# TCRME_lab3.net
KiCad netlist of a schematic drawn in Altium Designer
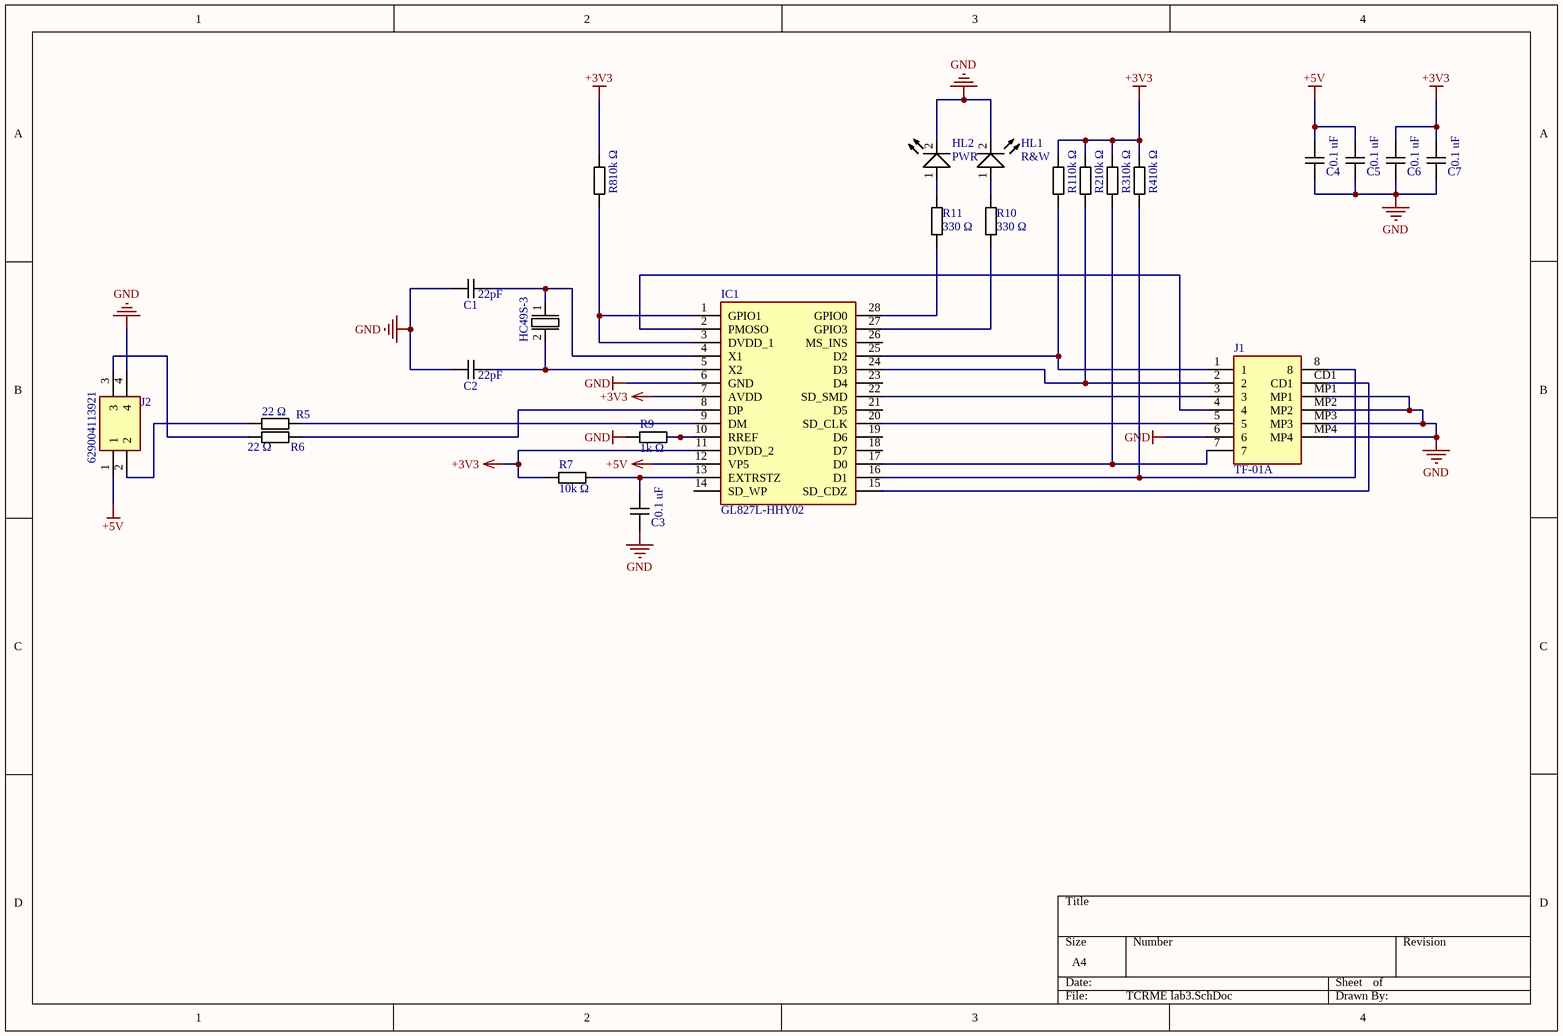
[diagram p0: TCRME lab3.SchDoc]

(export (version "E")
  (design (tool "Eeschema 10.0.6"))
  (components
    (comp (ref "C1")
      (value "22pF")
      (footprint "1206")
      (description "Cap Cer MLCC SMD 220pF 250V X7R 20% 1206")
      (fields
        (field (name "PART NUMBER") "1206B221M251CT")
        (field (name "MOUSER PART NUMBER") "791-1206B221M251CT")
      )
      (libsource (lib "SssAccesDatbase") (part "Cap"))
    )
    (comp (ref "C2")
      (value "22pF")
      (footprint "1206")
      (description "Cap Cer MLCC SMD 220pF 250V X7R 20% 1206")
      (fields
        (field (name "PART NUMBER") "1206B221M251CT")
        (field (name "MOUSER PART NUMBER") "791-1206B221M251CT")
      )
      (libsource (lib "SssAccesDatbase") (part "Cap"))
    )
    (comp (ref "C3")
      (value "0.1 uF")
      (footprint "1206")
      (description "Cap Cer MLCC SMD 220pF 250V X7R 20% 1206")
      (fields
        (field (name "PART NUMBER") "1206B221M251CT")
        (field (name "MOUSER PART NUMBER") "791-1206B221M251CT")
      )
      (libsource (lib "SssAccesDatbase") (part "Cap"))
    )
    (comp (ref "C4")
      (value "0.1 uF")
      (footprint "1206")
      (description "Cap Cer MLCC SMD 220pF 250V X7R 20% 1206")
      (fields
        (field (name "PART NUMBER") "1206B221M251CT")
        (field (name "MOUSER PART NUMBER") "791-1206B221M251CT")
      )
      (libsource (lib "SssAccesDatbase") (part "Cap"))
    )
    (comp (ref "C5")
      (value "0.1 uF")
      (footprint "1206")
      (description "Cap Cer MLCC SMD 220pF 250V X7R 20% 1206")
      (fields
        (field (name "PART NUMBER") "1206B221M251CT")
        (field (name "MOUSER PART NUMBER") "791-1206B221M251CT")
      )
      (libsource (lib "SssAccesDatbase") (part "Cap"))
    )
    (comp (ref "C6")
      (value "0.1 uF")
      (footprint "1206")
      (description "Cap Cer MLCC SMD 220pF 250V X7R 20% 1206")
      (fields
        (field (name "PART NUMBER") "1206B221M251CT")
        (field (name "MOUSER PART NUMBER") "791-1206B221M251CT")
      )
      (libsource (lib "SssAccesDatbase") (part "Cap"))
    )
    (comp (ref "C7")
      (value "0.1 uF")
      (footprint "1206")
      (description "Cap Cer MLCC SMD 220pF 250V X7R 20% 1206")
      (fields
        (field (name "PART NUMBER") "1206B221M251CT")
        (field (name "MOUSER PART NUMBER") "791-1206B221M251CT")
      )
      (libsource (lib "SssAccesDatbase") (part "Cap"))
    )
    (comp (ref "HL1")
      (value "R&W")
      (footprint "LED_3MM_GREEN")
      (fields (field (name "PART NUMBER") "FYL-5013 GD"))
      (libsource (lib "SssAccesDatbase") (part "LED_12"))
    )
    (comp (ref "HL2")
      (value "PWR")
      (footprint "LED_3MM_GREEN")
      (fields (field (name "PART NUMBER") "FYL-5013 GD"))
      (libsource (lib "SssAccesDatbase") (part "LED_12"))
    )
    (comp (ref "IC1")
      (value "GL827L-HHY02")
      (footprint "SamacSys:SOP64P600X175-28N")
      (description "Integrated Circuit")
      (libsource (lib "SamacSys") (part "GL827L-HHY02"))
    )
    (comp (ref "J1")
      (value "TF-01A")
      (footprint "SamacSys:TF01A")
      (description "Connector - Card Sockets 8 1.1mm SMD RoHS")
      (libsource (lib "SamacSys") (part "TF-01A"))
    )
    (comp (ref "J2")
      (value "629004113921")
      (footprint "SamacSys:629004113921")
      (description "Connector")
      (fields (field (name "MOUSER PART NUMBER") "710-629004113921"))
      (libsource (lib "*") (part "629004113921"))
    )
    (comp (ref "R1")
      (value "10k Ω")
      (footprint "RESC1608(0603)N")
      (description "RES SMD 0603 137k 1% 50ppm")
      (fields
        (field (name "PART NUMBER") "CPF0603F137KC1")
        (field (name "MOUSER PART NUMBER") "279-CPF0603F137KC1")
      )
      (libsource (lib "") (part "Resistor general_1"))
    )
    (comp (ref "R2")
      (value "10k Ω")
      (footprint "RESC1608(0603)N")
      (description "RES SMD 0603 137k 1% 50ppm")
      (fields
        (field (name "PART NUMBER") "CPF0603F137KC1")
        (field (name "MOUSER PART NUMBER") "279-CPF0603F137KC1")
      )
      (libsource (lib "") (part "Resistor general_1"))
    )
    (comp (ref "R3")
      (value "10k Ω")
      (footprint "RESC1608(0603)N")
      (description "RES SMD 0603 137k 1% 50ppm")
      (fields
        (field (name "PART NUMBER") "CPF0603F137KC1")
        (field (name "MOUSER PART NUMBER") "279-CPF0603F137KC1")
      )
      (libsource (lib "") (part "Resistor general_1"))
    )
    (comp (ref "R4")
      (value "10k Ω")
      (footprint "RESC1608(0603)N")
      (description "RES SMD 0603 137k 1% 50ppm")
      (fields
        (field (name "PART NUMBER") "CPF0603F137KC1")
        (field (name "MOUSER PART NUMBER") "279-CPF0603F137KC1")
      )
      (libsource (lib "") (part "Resistor general_1"))
    )
    (comp (ref "R5")
      (value "22 Ω")
      (footprint "RESC1608(0603)N")
      (description "RES SMD 0603 137k 1% 50ppm")
      (fields
        (field (name "PART NUMBER") "CPF0603F137KC1")
        (field (name "MOUSER PART NUMBER") "279-CPF0603F137KC1")
      )
      (libsource (lib "") (part "Resistor general_3"))
    )
    (comp (ref "R6")
      (value "22 Ω")
      (footprint "RESC1608(0603)N")
      (description "RES SMD 0603 137k 1% 50ppm")
      (fields
        (field (name "PART NUMBER") "CPF0603F137KC1")
        (field (name "MOUSER PART NUMBER") "279-CPF0603F137KC1")
      )
      (libsource (lib "") (part "Resistor general_2"))
    )
    (comp (ref "R7")
      (value "10k Ω")
      (footprint "RESC1608(0603)N")
      (description "RES SMD 0603 137k 1% 50ppm")
      (fields
        (field (name "PART NUMBER") "CPF0603F137KC1")
        (field (name "MOUSER PART NUMBER") "279-CPF0603F137KC1")
      )
      (libsource (lib "") (part "Resistor general_2"))
    )
    (comp (ref "R8")
      (value "10k Ω")
      (footprint "RESC1608(0603)N")
      (description "RES SMD 0603 137k 1% 50ppm")
      (fields
        (field (name "PART NUMBER") "CPF0603F137KC1")
        (field (name "MOUSER PART NUMBER") "279-CPF0603F137KC1")
      )
      (libsource (lib "") (part "Resistor general_1"))
    )
    (comp (ref "R9")
      (value "1k Ω")
      (footprint "RESC1608(0603)N")
      (description "RES SMD 0603 137k 1% 50ppm")
      (fields
        (field (name "PART NUMBER") "CPF0603F137KC1")
        (field (name "MOUSER PART NUMBER") "279-CPF0603F137KC1")
      )
      (libsource (lib "") (part "Resistor general_2"))
    )
    (comp (ref "R10")
      (value "330 Ω")
      (footprint "RESC1608(0603)N")
      (description "RES SMD 0603 137k 1% 50ppm")
      (fields
        (field (name "PART NUMBER") "CPF0603F137KC1")
        (field (name "MOUSER PART NUMBER") "279-CPF0603F137KC1")
      )
      (libsource (lib "SssAccesDatbase") (part "Resistor general"))
    )
    (comp (ref "R11")
      (value "330 Ω")
      (footprint "RESC1608(0603)N")
      (description "RES SMD 0603 137k 1% 50ppm")
      (fields
        (field (name "PART NUMBER") "CPF0603F137KC1")
        (field (name "MOUSER PART NUMBER") "279-CPF0603F137KC1")
      )
      (libsource (lib "SssAccesDatbase") (part "Resistor general"))
    )
    (comp (ref "Y1")
      (value "HC49S-3")
      (footprint "HC49S-3")
      (libsource (lib "Database_Libs2") (part "HC49S-3"))
    )
  )
  (nets
    (net (code "1") (name "+3V3") (class "Default")
      (node (ref "C6") (pin "2") (pinfunction "2_2") (pintype "passive"))
      (node (ref "C7") (pin "2") (pinfunction "2_2") (pintype "passive"))
      (node (ref "IC1") (pin "11") (pinfunction "DVDD_2_11") (pintype "passive"))
      (node (ref "IC1") (pin "7") (pinfunction "AVDD_7") (pintype "passive"))
      (node (ref "R1") (pin "2") (pinfunction "2_2") (pintype "passive"))
      (node (ref "R2") (pin "2") (pinfunction "2_2") (pintype "passive"))
      (node (ref "R3") (pin "2") (pinfunction "2_2") (pintype "passive"))
      (node (ref "R4") (pin "2") (pinfunction "2_2") (pintype "passive"))
      (node (ref "R7") (pin "2") (pinfunction "2_2") (pintype "passive"))
      (node (ref "R8") (pin "2") (pinfunction "2_2") (pintype "passive"))
    )
    (net (code "2") (name "+5V") (class "Default")
      (node (ref "C4") (pin "2") (pinfunction "2_2") (pintype "passive"))
      (node (ref "C5") (pin "2") (pinfunction "2_2") (pintype "passive"))
      (node (ref "IC1") (pin "12") (pinfunction "VP5_12") (pintype "passive"))
      (node (ref "J2") (pin "1") (pinfunction "1_1") (pintype "passive"))
    )
    (net (code "3") (name "GND") (class "Default")
      (node (ref "C1") (pin "1") (pinfunction "1_1") (pintype "passive"))
      (node (ref "C2") (pin "1") (pinfunction "1_1") (pintype "passive"))
      (node (ref "C3") (pin "1") (pinfunction "1_1") (pintype "passive"))
      (node (ref "C4") (pin "1") (pinfunction "1_1") (pintype "passive"))
      (node (ref "C5") (pin "1") (pinfunction "1_1") (pintype "passive"))
      (node (ref "C6") (pin "1") (pinfunction "1_1") (pintype "passive"))
      (node (ref "C7") (pin "1") (pinfunction "1_1") (pintype "passive"))
      (node (ref "HL1") (pin "2") (pinfunction "K_2") (pintype "passive"))
      (node (ref "HL2") (pin "2") (pinfunction "K_2") (pintype "passive"))
      (node (ref "IC1") (pin "6") (pinfunction "GND_6") (pintype "passive"))
      (node (ref "J1") (pin "6") (pinfunction "6_6") (pintype "passive"))
      (node (ref "J1") (pin "MP1") (pinfunction "MP1_MP1") (pintype "passive"))
      (node (ref "J1") (pin "MP2") (pinfunction "MP2_MP2") (pintype "passive"))
      (node (ref "J1") (pin "MP3") (pinfunction "MP3_MP3") (pintype "passive"))
      (node (ref "J1") (pin "MP4") (pinfunction "MP4_MP4") (pintype "passive"))
      (node (ref "J2") (pin "4") (pinfunction "4_4") (pintype "passive"))
      (node (ref "R9") (pin "2") (pinfunction "2_2") (pintype "passive"))
    )
    (net (code "4") (name "Net-(HL1-A)") (class "Default")
      (node (ref "HL1") (pin "1") (pinfunction "A_1") (pintype "passive"))
      (node (ref "R10") (pin "1") (pinfunction "1_1") (pintype "passive"))
    )
    (net (code "5") (name "Net-(HL2-A)") (class "Default")
      (node (ref "HL2") (pin "1") (pinfunction "A_1") (pintype "passive"))
      (node (ref "R11") (pin "1") (pinfunction "1_1") (pintype "passive"))
    )
    (net (code "6") (name "Net-(IC1-D0)") (class "Default")
      (node (ref "IC1") (pin "17") (pinfunction "D0_17") (pintype "passive"))
      (node (ref "J1") (pin "7") (pinfunction "7_7") (pintype "passive"))
      (node (ref "R3") (pin "1") (pinfunction "1_1") (pintype "passive"))
    )
    (net (code "7") (name "Net-(IC1-D1)") (class "Default")
      (node (ref "IC1") (pin "16") (pinfunction "D1_16") (pintype "passive"))
      (node (ref "J1") (pin "8") (pinfunction "8_8") (pintype "passive"))
      (node (ref "R4") (pin "1") (pinfunction "1_1") (pintype "passive"))
    )
    (net (code "8") (name "Net-(IC1-D2)") (class "Default")
      (node (ref "IC1") (pin "25") (pinfunction "D2_25") (pintype "passive"))
      (node (ref "J1") (pin "1") (pinfunction "1_1") (pintype "passive"))
      (node (ref "R1") (pin "1") (pinfunction "1_1") (pintype "passive"))
    )
    (net (code "9") (name "Net-(IC1-D3)") (class "Default")
      (node (ref "IC1") (pin "24") (pinfunction "D3_24") (pintype "passive"))
      (node (ref "J1") (pin "2") (pinfunction "2_2") (pintype "passive"))
      (node (ref "R2") (pin "1") (pinfunction "1_1") (pintype "passive"))
    )
    (net (code "10") (name "Net-(IC1-DM)") (class "Default")
      (node (ref "IC1") (pin "9") (pinfunction "DM_9") (pintype "passive"))
      (node (ref "R5") (pin "2") (pinfunction "2_2") (pintype "passive"))
    )
    (net (code "11") (name "Net-(IC1-DP)") (class "Default")
      (node (ref "IC1") (pin "8") (pinfunction "DP_8") (pintype "passive"))
      (node (ref "R6") (pin "1") (pinfunction "1_1") (pintype "passive"))
    )
    (net (code "12") (name "Net-(IC1-DVDD_1)") (class "Default")
      (node (ref "IC1") (pin "1") (pinfunction "GPIO1_1") (pintype "passive"))
      (node (ref "IC1") (pin "3") (pinfunction "DVDD_1_3") (pintype "passive"))
      (node (ref "R8") (pin "1") (pinfunction "1_1") (pintype "passive"))
    )
    (net (code "13") (name "Net-(IC1-EXTRSTZ)") (class "Default")
      (node (ref "C3") (pin "2") (pinfunction "2_2") (pintype "passive"))
      (node (ref "IC1") (pin "13") (pinfunction "EXTRSTZ_13") (pintype "passive"))
      (node (ref "R7") (pin "1") (pinfunction "1_1") (pintype "passive"))
    )
    (net (code "14") (name "Net-(IC1-GPIO0)") (class "Default")
      (node (ref "IC1") (pin "28") (pinfunction "GPIO0_28") (pintype "passive"))
      (node (ref "R11") (pin "2") (pinfunction "2_2") (pintype "passive"))
    )
    (net (code "15") (name "Net-(IC1-GPIO3)") (class "Default")
      (node (ref "IC1") (pin "27") (pinfunction "GPIO3_27") (pintype "passive"))
      (node (ref "R10") (pin "2") (pinfunction "2_2") (pintype "passive"))
    )
    (net (code "16") (name "Net-(IC1-PMOSO)") (class "Default")
      (node (ref "IC1") (pin "2") (pinfunction "PMOSO_2") (pintype "passive"))
      (node (ref "J1") (pin "4") (pinfunction "4_4") (pintype "passive"))
    )
    (net (code "17") (name "Net-(IC1-RREF)") (class "Default")
      (node (ref "IC1") (pin "10") (pinfunction "RREF_10") (pintype "passive"))
      (node (ref "R9") (pin "1") (pinfunction "1_1") (pintype "passive"))
    )
    (net (code "18") (name "Net-(IC1-SD_CDZ)") (class "Default")
      (node (ref "IC1") (pin "15") (pinfunction "SD_CDZ_15") (pintype "passive"))
      (node (ref "J1") (pin "CD1") (pinfunction "CD1_CD1") (pintype "passive"))
    )
    (net (code "19") (name "Net-(IC1-SD_CLK)") (class "Default")
      (node (ref "IC1") (pin "20") (pinfunction "SD_CLK_20") (pintype "passive"))
      (node (ref "J1") (pin "5") (pinfunction "5_5") (pintype "passive"))
    )
    (net (code "20") (name "Net-(IC1-SD_SMD)") (class "Default")
      (node (ref "IC1") (pin "22") (pinfunction "SD_SMD_22") (pintype "passive"))
      (node (ref "J1") (pin "3") (pinfunction "3_3") (pintype "passive"))
    )
    (net (code "21") (name "Net-(IC1-X1)") (class "Default")
      (node (ref "C1") (pin "2") (pinfunction "2_2") (pintype "passive"))
      (node (ref "IC1") (pin "4") (pinfunction "X1_4") (pintype "passive"))
      (node (ref "Y1") (pin "1") (pinfunction "15_1") (pintype "passive"))
    )
    (net (code "22") (name "Net-(IC1-X2)") (class "Default")
      (node (ref "C2") (pin "2") (pinfunction "2_2") (pintype "passive"))
      (node (ref "IC1") (pin "5") (pinfunction "X2_5") (pintype "passive"))
      (node (ref "Y1") (pin "2") (pinfunction "2_2") (pintype "passive"))
    )
    (net (code "23") (name "Net-(J2-Pad2)") (class "Default")
      (node (ref "J2") (pin "2") (pinfunction "2_2") (pintype "passive"))
      (node (ref "R5") (pin "1") (pinfunction "1_1") (pintype "passive"))
    )
    (net (code "24") (name "Net-(J2-Pad3)") (class "Default")
      (node (ref "J2") (pin "3") (pinfunction "3_3") (pintype "passive"))
      (node (ref "R6") (pin "2") (pinfunction "2_2") (pintype "passive"))
    )
    (net (code "25") (name "unconnected-(IC1-D4-Pad23)") (class "Default")
      (node (ref "IC1") (pin "23") (pinfunction "D4_23") (pintype "passive"))
    )
    (net (code "26") (name "unconnected-(IC1-D5-Pad21)") (class "Default")
      (node (ref "IC1") (pin "21") (pinfunction "D5_21") (pintype "passive"))
    )
    (net (code "27") (name "unconnected-(IC1-D6-Pad19)") (class "Default")
      (node (ref "IC1") (pin "19") (pinfunction "D6_19") (pintype "passive"))
    )
    (net (code "28") (name "unconnected-(IC1-D7-Pad18)") (class "Default")
      (node (ref "IC1") (pin "18") (pinfunction "D7_18") (pintype "passive"))
    )
    (net (code "29") (name "unconnected-(IC1-MS_INS-Pad26)") (class "Default")
      (node (ref "IC1") (pin "26") (pinfunction "MS_INS_26") (pintype "passive"))
    )
    (net (code "30") (name "unconnected-(IC1-SD_WP-Pad14)") (class "Default")
      (node (ref "IC1") (pin "14") (pinfunction "SD_WP_14") (pintype "passive"))
    )
  )
)
